# 2_MCU.net
KiCad netlist of a schematic drawn in Altium Designer
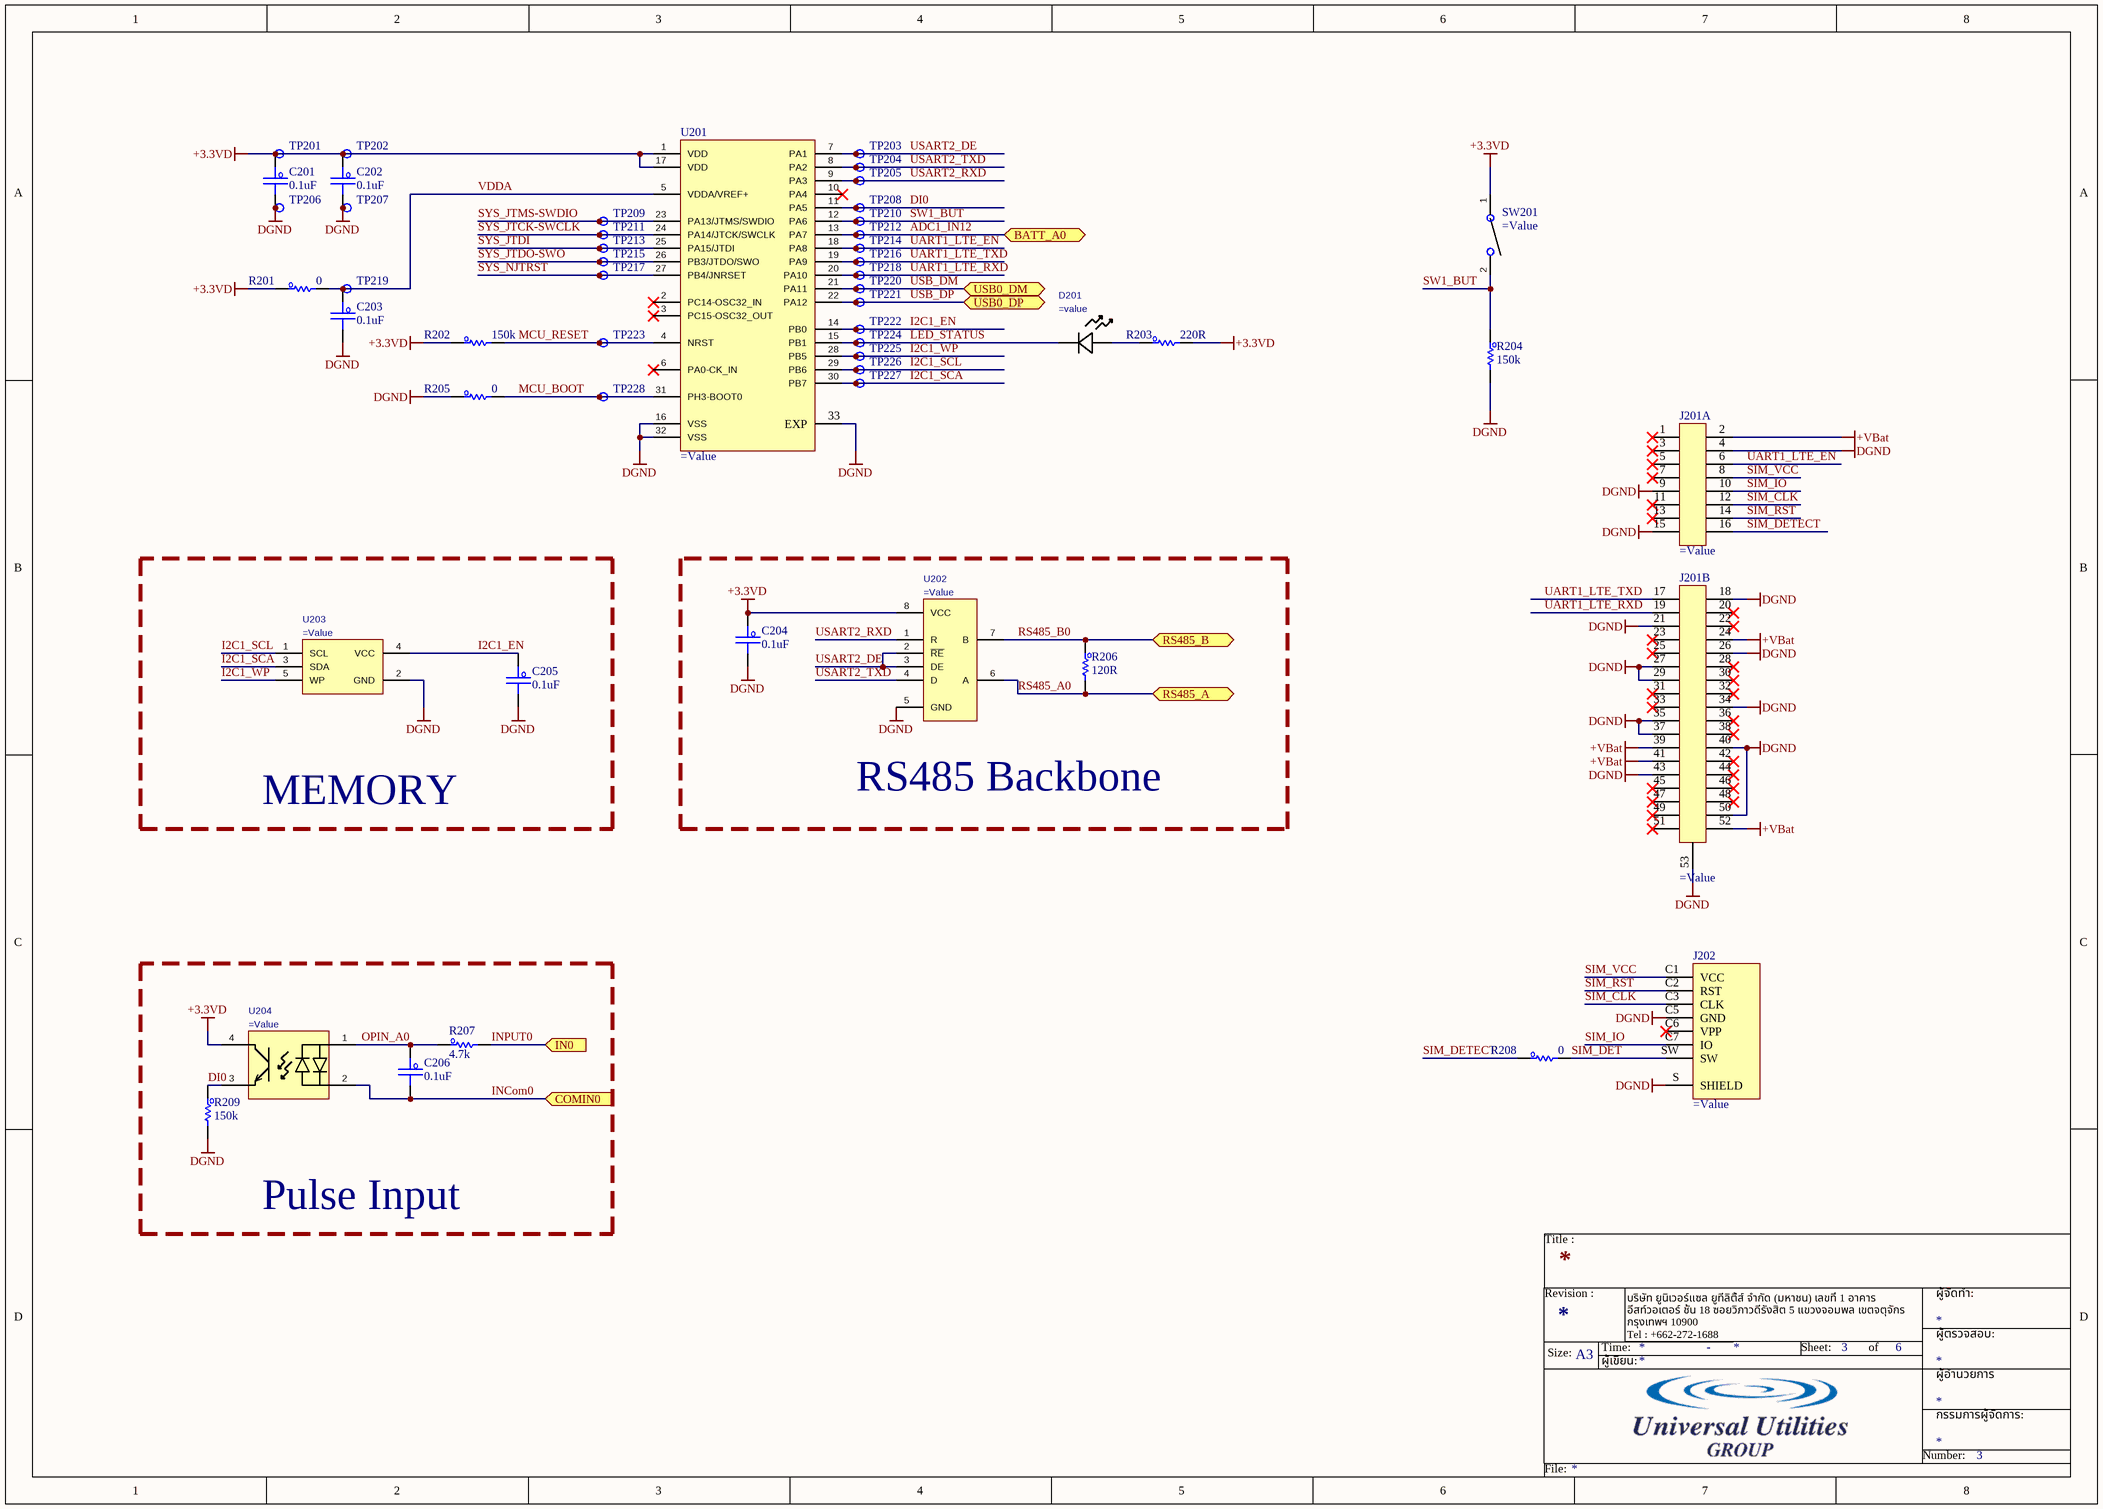
[diagram p0: 2_MCU.SchDoc]

(export (version "E")
  (design (tool "Eeschema 10.0.6"))
  (components
    (comp (ref "C201")
      (value "0.1uF")
      (footprint "C_0603")
      (description "CAP CER 0.1UF 50V X7R 0603")
      (fields (field (name "MANUFACTURER") "KEMET") (field (name "PARTNUMBER") "C0603C104K5RACTU"))
      (libsource (lib "UUSymbol") (part "C_Capacitor"))
    )
    (comp (ref "C202")
      (value "0.1uF")
      (footprint "C_0603")
      (description "CAP CER 0.1UF 50V X7R 0603")
      (fields (field (name "MANUFACTURER") "KEMET") (field (name "PARTNUMBER") "C0603C104K5RACTU"))
      (libsource (lib "UUSymbol") (part "C_Capacitor"))
    )
    (comp (ref "C203")
      (value "0.1uF")
      (footprint "C_0603")
      (description "CAP CER 0.1UF 50V X7R 0603")
      (fields (field (name "MANUFACTURER") "KEMET") (field (name "PARTNUMBER") "C0603C104K5RACTU"))
      (libsource (lib "UUSymbol") (part "C_Capacitor"))
    )
    (comp (ref "C204")
      (value "0.1uF")
      (footprint "C_0603")
      (description "CAP CER 0.1UF 50V X7R 0603")
      (fields (field (name "MANUFACTURER") "KEMET") (field (name "PARTNUMBER") "C0603C104K5RACTU"))
      (libsource (lib "UUSymbol") (part "C_Capacitor"))
    )
    (comp (ref "C205")
      (value "0.1uF")
      (footprint "C_0603")
      (description "CAP CER 0.1UF 50V X7R 0603")
      (fields (field (name "MANUFACTURER") "KEMET") (field (name "PARTNUMBER") "C0603C104K5RACTU"))
      (libsource (lib "UUSymbol") (part "C_Capacitor"))
    )
    (comp (ref "C206")
      (value "0.1uF")
      (footprint "C_0603")
      (description "CAP CER 0.1UF 50V X7R 0603")
      (fields (field (name "MANUFACTURER") "KEMET") (field (name "PARTNUMBER") "C0603C104K5RACTU"))
      (libsource (lib "UUSymbol") (part "C_Capacitor"))
    )
    (comp (ref "D201")
      (value "~")
      (footprint "LED_0VS75000_WRE")
      (description "LED BLUE CLEAR 0603 SMD")
      (fields (field (name "MANUFACTURER") "Wurth Electronics") (field (name "PARTNUMBER") "150060VS75000"))
      (libsource (lib "UUSymbol") (part "D_LED_150060BS75000"))
    )
    (comp (ref "J201")
      (value "~")
      (footprint "TE_2041119-1")
      (description "CONN PCI EXP MINI FEMALE 52POS")
      (fields
        (field (name "PARTNUMBER") "2041119-1")
        (field (name "MANUFACTURER") "TE Connectivity AMP Connectors")
      )
      (libsource (lib "UUSymbol") (part "CON_PCI-E-52P"))
    )
    (comp (ref "J202")
      (value "~")
      (footprint "SIM8060-6-1-14-00-A_REVA")
      (description "CONN SIM NANO HINGED 6P W/SWITCH")
      (fields (field (name "PARTNUMBER") "SIM8060-6-1-14-00-A") (field (name "MANUFACTURER") "GCT"))
      (libsource (lib "UUSymbol") (part "CON_SIM_Nano_Top"))
    )
    (comp (ref "R201")
      (value "0")
      (footprint "R_0603")
      (description "RES SMD 0 OHM JUMP 1/10W 0603")
      (fields (field (name "MANUFACTURER") "Vishay Dale") (field (name "PARTNUMBER") "CRCW06030000Z0EBC"))
      (libsource (lib "UUSymbol") (part "R_Resister"))
    )
    (comp (ref "R202")
      (value "150k")
      (footprint "R_0603")
      (description "RES SMD 150K OHM 1% 1/10W 0603")
      (fields (field (name "MANUFACTURER") "Vishay Dale") (field (name "PARTNUMBER") "CRCW0603150KFKEAC"))
      (libsource (lib "UUSymbol") (part "R_Resister"))
    )
    (comp (ref "R203")
      (value "220R")
      (footprint "R_0603")
      (description "RES SMD 220 OHM 1% 1/10W 0603")
      (fields (field (name "MANUFACTURER") "Vishay Dale") (field (name "PARTNUMBER") "CRCW0603220RFKEAC"))
      (libsource (lib "UUSymbol") (part "R_Resister"))
    )
    (comp (ref "R204")
      (value "150k")
      (footprint "R_0603")
      (description "RES SMD 150K OHM 1% 1/10W 0603")
      (fields (field (name "MANUFACTURER") "Vishay Dale") (field (name "PARTNUMBER") "CRCW0603150KFKEAC"))
      (libsource (lib "UUSymbol") (part "R_Resister"))
    )
    (comp (ref "R205")
      (value "0")
      (footprint "R_0603")
      (description "RES SMD 0 OHM JUMP 1/10W 0603")
      (fields (field (name "MANUFACTURER") "Vishay Dale") (field (name "PARTNUMBER") "CRCW06030000Z0EBC"))
      (libsource (lib "UUSymbol") (part "R_Resister"))
    )
    (comp (ref "R206")
      (value "120R")
      (footprint "R_0603")
      (description "RES SMD 120 OHM 1% 1/3W 0603")
      (fields (field (name "MANUFACTURER") "Vishay Dale") (field (name "PARTNUMBER") "CRCW0603120RFKEAHP"))
      (libsource (lib "UUSymbol") (part "R_Resister"))
    )
    (comp (ref "R207")
      (value "4.7k")
      (footprint "R_0603")
      (description "RES 4.7K OHM 5% 1/10W 0603")
      (fields (field (name "MANUFACTURER") "Vishay Dale") (field (name "PARTNUMBER") "CRCW06034K70JNEBC"))
      (libsource (lib "UUSymbol") (part "R_Resister"))
    )
    (comp (ref "R208")
      (value "0")
      (footprint "R_0603")
      (description "RES SMD 0 OHM JUMP 1/10W 0603")
      (fields (field (name "MANUFACTURER") "Vishay Dale") (field (name "PARTNUMBER") "CRCW06030000Z0EBC"))
      (libsource (lib "UUSymbol") (part "R_Resister"))
    )
    (comp (ref "R209")
      (value "150k")
      (footprint "R_0603")
      (description "RES SMD 150K OHM 1% 1/10W 0603")
      (fields (field (name "MANUFACTURER") "Vishay Dale") (field (name "PARTNUMBER") "CRCW0603150KFKEAC"))
      (libsource (lib "UUSymbol") (part "R_Resister"))
    )
    (comp (ref "SW201")
      (value "~")
      (footprint "SW_KSS241GLFS_CN")
      (description "SWITCH TACTILE SPST-NO 0.05A 50V")
      (fields (field (name "PARTNUMBER") "KSS241GLFS") (field (name "MANUFACTURER") "C&K"))
      (libsource (lib "UUSymbol") (part "SW_TAC"))
    )
    (comp (ref "TP201")
      (value "~")
      (footprint "TP_Testpoint")
      (description "TestPoint")
      (libsource (lib "UUSymbol") (part "TP_TestPoint"))
    )
    (comp (ref "TP202")
      (value "~")
      (footprint "TP_Testpoint")
      (description "TestPoint")
      (libsource (lib "UUSymbol") (part "TP_TestPoint"))
    )
    (comp (ref "TP203")
      (value "~")
      (footprint "TP_Testpoint")
      (description "TestPoint")
      (libsource (lib "UUSymbol") (part "TP_TestPoint"))
    )
    (comp (ref "TP204")
      (value "~")
      (footprint "TP_Testpoint")
      (description "TestPoint")
      (libsource (lib "UUSymbol") (part "TP_TestPoint"))
    )
    (comp (ref "TP205")
      (value "~")
      (footprint "TP_Testpoint")
      (description "TestPoint")
      (libsource (lib "UUSymbol") (part "TP_TestPoint"))
    )
    (comp (ref "TP206")
      (value "~")
      (footprint "TP_Testpoint")
      (description "TestPoint")
      (libsource (lib "UUSymbol") (part "TP_TestPoint"))
    )
    (comp (ref "TP207")
      (value "~")
      (footprint "TP_Testpoint")
      (description "TestPoint")
      (libsource (lib "UUSymbol") (part "TP_TestPoint"))
    )
    (comp (ref "TP208")
      (value "~")
      (footprint "TP_Testpoint")
      (description "TestPoint")
      (libsource (lib "UUSymbol") (part "TP_TestPoint"))
    )
    (comp (ref "TP209")
      (value "~")
      (footprint "TP_Testpoint")
      (description "TestPoint")
      (libsource (lib "UUSymbol") (part "TP_TestPoint"))
    )
    (comp (ref "TP210")
      (value "~")
      (footprint "TP_Testpoint")
      (description "TestPoint")
      (libsource (lib "UUSymbol") (part "TP_TestPoint"))
    )
    (comp (ref "TP211")
      (value "~")
      (footprint "TP_Testpoint")
      (description "TestPoint")
      (libsource (lib "UUSymbol") (part "TP_TestPoint"))
    )
    (comp (ref "TP212")
      (value "~")
      (footprint "TP_Testpoint")
      (description "TestPoint")
      (libsource (lib "UUSymbol") (part "TP_TestPoint"))
    )
    (comp (ref "TP213")
      (value "~")
      (footprint "TP_Testpoint")
      (description "TestPoint")
      (libsource (lib "UUSymbol") (part "TP_TestPoint"))
    )
    (comp (ref "TP214")
      (value "~")
      (footprint "TP_Testpoint")
      (description "TestPoint")
      (libsource (lib "UUSymbol") (part "TP_TestPoint"))
    )
    (comp (ref "TP215")
      (value "~")
      (footprint "TP_Testpoint")
      (description "TestPoint")
      (libsource (lib "UUSymbol") (part "TP_TestPoint"))
    )
    (comp (ref "TP216")
      (value "~")
      (footprint "TP_Testpoint")
      (description "TestPoint")
      (libsource (lib "UUSymbol") (part "TP_TestPoint"))
    )
    (comp (ref "TP217")
      (value "~")
      (footprint "TP_Testpoint")
      (description "TestPoint")
      (libsource (lib "UUSymbol") (part "TP_TestPoint"))
    )
    (comp (ref "TP218")
      (value "~")
      (footprint "TP_Testpoint")
      (description "TestPoint")
      (libsource (lib "UUSymbol") (part "TP_TestPoint"))
    )
    (comp (ref "TP219")
      (value "~")
      (footprint "TP_Testpoint")
      (description "TestPoint")
      (libsource (lib "UUSymbol") (part "TP_TestPoint"))
    )
    (comp (ref "TP220")
      (value "~")
      (footprint "TP_Testpoint")
      (description "TestPoint")
      (libsource (lib "UUSymbol") (part "TP_TestPoint"))
    )
    (comp (ref "TP221")
      (value "~")
      (footprint "TP_Testpoint")
      (description "TestPoint")
      (libsource (lib "UUSymbol") (part "TP_TestPoint"))
    )
    (comp (ref "TP222")
      (value "~")
      (footprint "TP_Testpoint")
      (description "TestPoint")
      (libsource (lib "UUSymbol") (part "TP_TestPoint"))
    )
    (comp (ref "TP223")
      (value "~")
      (footprint "TP_Testpoint")
      (description "TestPoint")
      (libsource (lib "UUSymbol") (part "TP_TestPoint"))
    )
    (comp (ref "TP224")
      (value "~")
      (footprint "TP_Testpoint")
      (description "TestPoint")
      (libsource (lib "UUSymbol") (part "TP_TestPoint"))
    )
    (comp (ref "TP225")
      (value "~")
      (footprint "TP_Testpoint")
      (description "TestPoint")
      (libsource (lib "UUSymbol") (part "TP_TestPoint"))
    )
    (comp (ref "TP226")
      (value "~")
      (footprint "TP_Testpoint")
      (description "TestPoint")
      (libsource (lib "UUSymbol") (part "TP_TestPoint"))
    )
    (comp (ref "TP227")
      (value "~")
      (footprint "TP_Testpoint")
      (description "TestPoint")
      (libsource (lib "UUSymbol") (part "TP_TestPoint"))
    )
    (comp (ref "TP228")
      (value "~")
      (footprint "TP_Testpoint")
      (description "TestPoint")
      (libsource (lib "UUSymbol") (part "TP_TestPoint"))
    )
    (comp (ref "U201")
      (value "~")
      (footprint "QFN50P500X500X60-33N")
      (description "IC MCU 32BIT 256KB FLSH 32UFQFPN")
      (fields (field (name "PARTNUMBER") "STM32L432KCU6") (field (name "MANUFACTURER") "STMicroelectronics"))
      (libsource (lib "UUSymbol") (part "IC_MCU_STM32L432"))
    )
    (comp (ref "U202")
      (value "~")
      (footprint "D0008A_L")
      (description "IC TRANSCEIVER HALF 1/1 8SOIC")
      (fields (field (name "MANUFACTURER") "Texas Instruments") (field (name "PARTNUMBER") "SN65HVD11DR"))
      (libsource (lib "UUSymbol") (part "IC_TRAN_THVD1505DR"))
    )
    (comp (ref "U203")
      (value "~")
      (footprint "SOT65P210X110-5N")
      (description "IC EEPROM 2KBIT I2C SC70-5")
      (fields
        (field (name "MANUFACTURER") "Microchip Technology")
        (field (name "PARTNUMBER") "24AA02HT-I/LT")
      )
      (libsource (lib "UUSymbol") (part "IC_MEM_24AA02HT"))
    )
    (comp (ref "U204")
      (value "~")
      (footprint "SOIC_M618A-3T_VI")
      (description "OPTOISOLATR 5KV TRANSISTOR 4-SMD")
      (fields (field (name "MANUFACTURER") "Lite-On Inc.") (field (name "PARTNUMBER") "LTV-814S-TA1"))
      (libsource (lib "UUSymbol") (part "IC_OPTO_LTV-814S-TA1"))
    )
  )
  (nets
    (net (code "1") (name "+3.3VD") (class "Default")
      (node (ref "C201") (pin "1") (pinfunction "1_1") (pintype "passive"))
      (node (ref "C202") (pin "1") (pinfunction "1_1") (pintype "passive"))
      (node (ref "C204") (pin "1") (pinfunction "1_1") (pintype "passive"))
      (node (ref "R201") (pin "1") (pinfunction "1_1") (pintype "passive"))
      (node (ref "R202") (pin "1") (pinfunction "1_1") (pintype "passive"))
      (node (ref "R203") (pin "2") (pinfunction "2_2") (pintype "passive"))
      (node (ref "SW201") (pin "1") (pinfunction "1_1") (pintype "passive"))
      (node (ref "TP201") (pin "1") (pinfunction "1_1") (pintype "passive"))
      (node (ref "TP202") (pin "1") (pinfunction "1_1") (pintype "passive"))
      (node (ref "U201") (pin "1") (pinfunction "VDD_1") (pintype "passive"))
      (node (ref "U201") (pin "17") (pinfunction "VDD_17") (pintype "passive"))
      (node (ref "U202") (pin "8") (pinfunction "VCC_8") (pintype "passive"))
      (node (ref "U204") (pin "4") (pinfunction "C_4") (pintype "passive"))
    )
    (net (code "2") (name "+VBat") (class "Default")
      (node (ref "J201") (pin "2") (pinfunction "2_2") (pintype "passive"))
      (node (ref "J201") (pin "24") (pinfunction "24_24") (pintype "passive"))
      (node (ref "J201") (pin "39") (pinfunction "39_39") (pintype "passive"))
      (node (ref "J201") (pin "41") (pinfunction "41_41") (pintype "passive"))
      (node (ref "J201") (pin "52") (pinfunction "52_52") (pintype "passive"))
    )
    (net (code "3") (name "/ADC1_IN12") (class "Default")
      (node (ref "TP212") (pin "1") (pinfunction "1_1") (pintype "passive"))
      (node (ref "U201") (pin "13") (pinfunction "PA7_13") (pintype "passive"))
    )
    (net (code "4") (name "/DI0") (class "Default")
      (node (ref "R209") (pin "1") (pinfunction "1_1") (pintype "passive"))
      (node (ref "TP208") (pin "1") (pinfunction "1_1") (pintype "passive"))
      (node (ref "U201") (pin "11") (pinfunction "PA5_11") (pintype "passive"))
      (node (ref "U204") (pin "3") (pinfunction "E_3") (pintype "passive"))
    )
    (net (code "5") (name "/I2C1_EN") (class "Default")
      (node (ref "C205") (pin "1") (pinfunction "1_1") (pintype "passive"))
      (node (ref "TP222") (pin "1") (pinfunction "1_1") (pintype "passive"))
      (node (ref "U201") (pin "14") (pinfunction "PB0_14") (pintype "passive"))
      (node (ref "U203") (pin "4") (pinfunction "VCC_4") (pintype "passive"))
    )
    (net (code "6") (name "/I2C1_SCA") (class "Default")
      (node (ref "TP227") (pin "1") (pinfunction "1_1") (pintype "passive"))
      (node (ref "U201") (pin "30") (pinfunction "PB7_30") (pintype "passive"))
      (node (ref "U203") (pin "3") (pinfunction "SDA_3") (pintype "passive"))
    )
    (net (code "7") (name "/I2C1_SCL") (class "Default")
      (node (ref "TP226") (pin "1") (pinfunction "1_1") (pintype "passive"))
      (node (ref "U201") (pin "29") (pinfunction "PB6_29") (pintype "passive"))
      (node (ref "U203") (pin "1") (pinfunction "SCL_1") (pintype "passive"))
    )
    (net (code "8") (name "/I2C1_WP") (class "Default")
      (node (ref "TP225") (pin "1") (pinfunction "1_1") (pintype "passive"))
      (node (ref "U201") (pin "28") (pinfunction "PB5_28") (pintype "passive"))
      (node (ref "U203") (pin "5") (pinfunction "WP_5") (pintype "passive"))
    )
    (net (code "9") (name "/INCom0") (class "Default")
      (node (ref "C206") (pin "2") (pinfunction "2_2") (pintype "passive"))
      (node (ref "U204") (pin "2") (pinfunction "C_2_2") (pintype "passive"))
    )
    (net (code "10") (name "/INPUT0") (class "Default")
      (node (ref "R207") (pin "2") (pinfunction "2_2") (pintype "passive"))
    )
    (net (code "11") (name "/LED_STATUS") (class "Default")
      (node (ref "D201") (pin "2") (pinfunction "2_2") (pintype "passive"))
      (node (ref "TP224") (pin "1") (pinfunction "1_1") (pintype "passive"))
      (node (ref "U201") (pin "15") (pinfunction "PB1_15") (pintype "passive"))
    )
    (net (code "12") (name "/MCU_BOOT") (class "Default")
      (node (ref "R205") (pin "2") (pinfunction "2_2") (pintype "passive"))
      (node (ref "TP228") (pin "1") (pinfunction "1_1") (pintype "passive"))
      (node (ref "U201") (pin "31") (pinfunction "PH3-BOOT0_31") (pintype "passive"))
    )
    (net (code "13") (name "/MCU_RESET") (class "Default")
      (node (ref "R202") (pin "2") (pinfunction "2_2") (pintype "passive"))
      (node (ref "TP223") (pin "1") (pinfunction "1_1") (pintype "passive"))
      (node (ref "U201") (pin "4") (pinfunction "NRST_4") (pintype "passive"))
    )
    (net (code "14") (name "/OPIN_A0") (class "Default")
      (node (ref "C206") (pin "1") (pinfunction "1_1") (pintype "passive"))
      (node (ref "R207") (pin "1") (pinfunction "1_1") (pintype "passive"))
      (node (ref "U204") (pin "1") (pinfunction "A_1") (pintype "passive"))
    )
    (net (code "15") (name "/RS485_A0") (class "Default")
      (node (ref "R206") (pin "2") (pinfunction "2_2") (pintype "passive"))
      (node (ref "U202") (pin "6") (pinfunction "A_6") (pintype "passive"))
    )
    (net (code "16") (name "/RS485_B0") (class "Default")
      (node (ref "R206") (pin "1") (pinfunction "1_1") (pintype "passive"))
      (node (ref "U202") (pin "7") (pinfunction "B_7") (pintype "passive"))
    )
    (net (code "17") (name "/SIM_CLK") (class "Default")
      (node (ref "J201") (pin "12") (pinfunction "12_12") (pintype "passive"))
      (node (ref "J202") (pin "C3") (pinfunction "CLK_C3") (pintype "passive"))
    )
    (net (code "18") (name "/SIM_DET") (class "Default")
      (node (ref "J202") (pin "SW") (pinfunction "SW_SW") (pintype "passive"))
      (node (ref "R208") (pin "2") (pinfunction "2_2") (pintype "passive"))
    )
    (net (code "19") (name "/SIM_DETECT") (class "Default")
      (node (ref "J201") (pin "16") (pinfunction "16_16") (pintype "passive"))
      (node (ref "R208") (pin "1") (pinfunction "1_1") (pintype "passive"))
    )
    (net (code "20") (name "/SIM_IO") (class "Default")
      (node (ref "J201") (pin "10") (pinfunction "10_10") (pintype "passive"))
      (node (ref "J202") (pin "C7") (pinfunction "IO_C7") (pintype "passive"))
    )
    (net (code "21") (name "/SIM_RST") (class "Default")
      (node (ref "J201") (pin "14") (pinfunction "14_14") (pintype "passive"))
      (node (ref "J202") (pin "C2") (pinfunction "RST_C2") (pintype "passive"))
    )
    (net (code "22") (name "/SIM_VCC") (class "Default")
      (node (ref "J201") (pin "8") (pinfunction "8_8") (pintype "passive"))
      (node (ref "J202") (pin "C1") (pinfunction "VCC_C1") (pintype "passive"))
    )
    (net (code "23") (name "/SW1_BUT") (class "Default")
      (node (ref "R204") (pin "1") (pinfunction "1_1") (pintype "passive"))
      (node (ref "SW201") (pin "2") (pinfunction "2_2") (pintype "passive"))
      (node (ref "TP210") (pin "1") (pinfunction "1_1") (pintype "passive"))
      (node (ref "U201") (pin "12") (pinfunction "PA6_12") (pintype "passive"))
    )
    (net (code "24") (name "/SYS_JTCK-SWCLK") (class "Default")
      (node (ref "TP211") (pin "1") (pinfunction "1_1") (pintype "passive"))
      (node (ref "U201") (pin "24") (pinfunction "PA14/JTCK/SWCLK_24") (pintype "passive"))
    )
    (net (code "25") (name "/SYS_JTDI") (class "Default")
      (node (ref "TP213") (pin "1") (pinfunction "1_1") (pintype "passive"))
      (node (ref "U201") (pin "25") (pinfunction "PA15/JTDI_25") (pintype "passive"))
    )
    (net (code "26") (name "/SYS_JTDO-SWO") (class "Default")
      (node (ref "TP215") (pin "1") (pinfunction "1_1") (pintype "passive"))
      (node (ref "U201") (pin "26") (pinfunction "PB3/JTDO/SWO_26") (pintype "passive"))
    )
    (net (code "27") (name "/SYS_JTMS-SWDIO") (class "Default")
      (node (ref "TP209") (pin "1") (pinfunction "1_1") (pintype "passive"))
      (node (ref "U201") (pin "23") (pinfunction "PA13/JTMS/SWDIO_23") (pintype "passive"))
    )
    (net (code "28") (name "/SYS_NJTRST") (class "Default")
      (node (ref "TP217") (pin "1") (pinfunction "1_1") (pintype "passive"))
      (node (ref "U201") (pin "27") (pinfunction "PB4/JNRSET_27") (pintype "passive"))
    )
    (net (code "29") (name "/UART1_LTE_EN") (class "Default")
      (node (ref "J201") (pin "6") (pinfunction "6_6") (pintype "passive"))
      (node (ref "TP214") (pin "1") (pinfunction "1_1") (pintype "passive"))
      (node (ref "U201") (pin "18") (pinfunction "PA8_18") (pintype "passive"))
    )
    (net (code "30") (name "/UART1_LTE_RXD") (class "Default")
      (node (ref "J201") (pin "19") (pinfunction "19_19") (pintype "passive"))
      (node (ref "TP218") (pin "1") (pinfunction "1_1") (pintype "passive"))
      (node (ref "U201") (pin "20") (pinfunction "PA10_20") (pintype "passive"))
    )
    (net (code "31") (name "/UART1_LTE_TXD") (class "Default")
      (node (ref "J201") (pin "17") (pinfunction "17_17") (pintype "passive"))
      (node (ref "TP216") (pin "1") (pinfunction "1_1") (pintype "passive"))
      (node (ref "U201") (pin "19") (pinfunction "PA9_19") (pintype "passive"))
    )
    (net (code "32") (name "/USART2_DE") (class "Default")
      (node (ref "TP203") (pin "1") (pinfunction "1_1") (pintype "passive"))
      (node (ref "U201") (pin "7") (pinfunction "PA1_7") (pintype "passive"))
      (node (ref "U202") (pin "2") (pinfunction "~{RE}_2") (pintype "passive"))
      (node (ref "U202") (pin "3") (pinfunction "DE_3") (pintype "passive"))
    )
    (net (code "33") (name "/USART2_RXD") (class "Default")
      (node (ref "TP205") (pin "1") (pinfunction "1_1") (pintype "passive"))
      (node (ref "U201") (pin "9") (pinfunction "PA3_9") (pintype "passive"))
      (node (ref "U202") (pin "1") (pinfunction "R_1") (pintype "passive"))
    )
    (net (code "34") (name "/USART2_TXD") (class "Default")
      (node (ref "TP204") (pin "1") (pinfunction "1_1") (pintype "passive"))
      (node (ref "U201") (pin "8") (pinfunction "PA2_8") (pintype "passive"))
      (node (ref "U202") (pin "4") (pinfunction "D_4") (pintype "passive"))
    )
    (net (code "35") (name "/USB_DM") (class "Default")
      (node (ref "TP220") (pin "1") (pinfunction "1_1") (pintype "passive"))
      (node (ref "U201") (pin "21") (pinfunction "PA11_21") (pintype "passive"))
    )
    (net (code "36") (name "/USB_DP") (class "Default")
      (node (ref "TP221") (pin "1") (pinfunction "1_1") (pintype "passive"))
      (node (ref "U201") (pin "22") (pinfunction "PA12_22") (pintype "passive"))
    )
    (net (code "37") (name "/VDDA") (class "Default")
      (node (ref "C203") (pin "1") (pinfunction "1_1") (pintype "passive"))
      (node (ref "R201") (pin "2") (pinfunction "2_2") (pintype "passive"))
      (node (ref "TP219") (pin "1") (pinfunction "1_1") (pintype "passive"))
      (node (ref "U201") (pin "5") (pinfunction "VDDA/VREF+_5") (pintype "passive"))
    )
    (net (code "38") (name "DGND") (class "Default")
      (node (ref "C201") (pin "2") (pinfunction "2_2") (pintype "passive"))
      (node (ref "C202") (pin "2") (pinfunction "2_2") (pintype "passive"))
      (node (ref "C203") (pin "2") (pinfunction "2_2") (pintype "passive"))
      (node (ref "C204") (pin "2") (pinfunction "2_2") (pintype "passive"))
      (node (ref "C205") (pin "2") (pinfunction "2_2") (pintype "passive"))
      (node (ref "J201") (pin "15") (pinfunction "15_15") (pintype "passive"))
      (node (ref "J201") (pin "18") (pinfunction "18_18") (pintype "passive"))
      (node (ref "J201") (pin "21") (pinfunction "21_21") (pintype "passive"))
      (node (ref "J201") (pin "26") (pinfunction "26_26") (pintype "passive"))
      (node (ref "J201") (pin "27") (pinfunction "27_27") (pintype "passive"))
      (node (ref "J201") (pin "29") (pinfunction "29_29") (pintype "passive"))
      (node (ref "J201") (pin "34") (pinfunction "34_34") (pintype "passive"))
      (node (ref "J201") (pin "35") (pinfunction "35_35") (pintype "passive"))
      (node (ref "J201") (pin "37") (pinfunction "37_37") (pintype "passive"))
      (node (ref "J201") (pin "4") (pinfunction "4_4") (pintype "passive"))
      (node (ref "J201") (pin "40") (pinfunction "40_40") (pintype "passive"))
      (node (ref "J201") (pin "43") (pinfunction "43_43") (pintype "passive"))
      (node (ref "J201") (pin "50") (pinfunction "50_50") (pintype "passive"))
      (node (ref "J201") (pin "53") (pinfunction "53_53") (pintype "passive"))
      (node (ref "J201") (pin "9") (pinfunction "9_9") (pintype "passive"))
      (node (ref "J202") (pin "C5") (pinfunction "GND_C5") (pintype "passive"))
      (node (ref "J202") (pin "S") (pinfunction "SHIELD_S") (pintype "passive"))
      (node (ref "R204") (pin "2") (pinfunction "2_2") (pintype "passive"))
      (node (ref "R205") (pin "1") (pinfunction "1_1") (pintype "passive"))
      (node (ref "R209") (pin "2") (pinfunction "2_2") (pintype "passive"))
      (node (ref "TP206") (pin "1") (pinfunction "1_1") (pintype "passive"))
      (node (ref "TP207") (pin "1") (pinfunction "1_1") (pintype "passive"))
      (node (ref "U201") (pin "16") (pinfunction "VSS_16") (pintype "passive"))
      (node (ref "U201") (pin "32") (pinfunction "VSS_32") (pintype "passive"))
      (node (ref "U201") (pin "33") (pinfunction "EXP_33") (pintype "passive"))
      (node (ref "U202") (pin "5") (pinfunction "GND_5") (pintype "passive"))
      (node (ref "U203") (pin "2") (pinfunction "GND_2") (pintype "passive"))
    )
    (net (code "39") (name "Net-(D201-Pad1)") (class "Default")
      (node (ref "D201") (pin "1") (pinfunction "1_1") (pintype "passive"))
      (node (ref "R203") (pin "1") (pinfunction "1_1") (pintype "passive"))
    )
    (net (code "40") (name "unconnected-(J201-Pad1)") (class "Default")
      (node (ref "J201") (pin "1") (pinfunction "1_1") (pintype "passive+no_connect"))
    )
    (net (code "41") (name "unconnected-(J201-Pad3)") (class "Default")
      (node (ref "J201") (pin "3") (pinfunction "3_3") (pintype "passive+no_connect"))
    )
    (net (code "42") (name "unconnected-(J201-Pad5)") (class "Default")
      (node (ref "J201") (pin "5") (pinfunction "5_5") (pintype "passive+no_connect"))
    )
    (net (code "43") (name "unconnected-(J201-Pad7)") (class "Default")
      (node (ref "J201") (pin "7") (pinfunction "7_7") (pintype "passive+no_connect"))
    )
    (net (code "44") (name "unconnected-(J201-Pad11)") (class "Default")
      (node (ref "J201") (pin "11") (pinfunction "11_11") (pintype "passive+no_connect"))
    )
    (net (code "45") (name "unconnected-(J201-Pad13)") (class "Default")
      (node (ref "J201") (pin "13") (pinfunction "13_13") (pintype "passive+no_connect"))
    )
    (net (code "46") (name "unconnected-(J201-Pad20)") (class "Default")
      (node (ref "J201") (pin "20") (pinfunction "20_20") (pintype "passive+no_connect"))
    )
    (net (code "47") (name "unconnected-(J201-Pad22)") (class "Default")
      (node (ref "J201") (pin "22") (pinfunction "22_22") (pintype "passive+no_connect"))
    )
    (net (code "48") (name "unconnected-(J201-Pad23)") (class "Default")
      (node (ref "J201") (pin "23") (pinfunction "23_23") (pintype "passive+no_connect"))
    )
    (net (code "49") (name "unconnected-(J201-Pad25)") (class "Default")
      (node (ref "J201") (pin "25") (pinfunction "25_25") (pintype "passive+no_connect"))
    )
    (net (code "50") (name "unconnected-(J201-Pad28)") (class "Default")
      (node (ref "J201") (pin "28") (pinfunction "28_28") (pintype "passive+no_connect"))
    )
    (net (code "51") (name "unconnected-(J201-Pad30)") (class "Default")
      (node (ref "J201") (pin "30") (pinfunction "30_30") (pintype "passive+no_connect"))
    )
    (net (code "52") (name "unconnected-(J201-Pad31)") (class "Default")
      (node (ref "J201") (pin "31") (pinfunction "31_31") (pintype "passive+no_connect"))
    )
    (net (code "53") (name "unconnected-(J201-Pad32)") (class "Default")
      (node (ref "J201") (pin "32") (pinfunction "32_32") (pintype "passive+no_connect"))
    )
    (net (code "54") (name "unconnected-(J201-Pad33)") (class "Default")
      (node (ref "J201") (pin "33") (pinfunction "33_33") (pintype "passive+no_connect"))
    )
    (net (code "55") (name "unconnected-(J201-Pad36)") (class "Default")
      (node (ref "J201") (pin "36") (pinfunction "36_36") (pintype "passive+no_connect"))
    )
    (net (code "56") (name "unconnected-(J201-Pad38)") (class "Default")
      (node (ref "J201") (pin "38") (pinfunction "38_38") (pintype "passive+no_connect"))
    )
    (net (code "57") (name "unconnected-(J201-Pad42)") (class "Default")
      (node (ref "J201") (pin "42") (pinfunction "42_42") (pintype "passive+no_connect"))
    )
    (net (code "58") (name "unconnected-(J201-Pad44)") (class "Default")
      (node (ref "J201") (pin "44") (pinfunction "44_44") (pintype "passive+no_connect"))
    )
    (net (code "59") (name "unconnected-(J201-Pad45)") (class "Default")
      (node (ref "J201") (pin "45") (pinfunction "45_45") (pintype "passive+no_connect"))
    )
    (net (code "60") (name "unconnected-(J201-Pad46)") (class "Default")
      (node (ref "J201") (pin "46") (pinfunction "46_46") (pintype "passive+no_connect"))
    )
    (net (code "61") (name "unconnected-(J201-Pad47)") (class "Default")
      (node (ref "J201") (pin "47") (pinfunction "47_47") (pintype "passive+no_connect"))
    )
    (net (code "62") (name "unconnected-(J201-Pad48)") (class "Default")
      (node (ref "J201") (pin "48") (pinfunction "48_48") (pintype "passive+no_connect"))
    )
    (net (code "63") (name "unconnected-(J201-Pad49)") (class "Default")
      (node (ref "J201") (pin "49") (pinfunction "49_49") (pintype "passive+no_connect"))
    )
    (net (code "64") (name "unconnected-(J201-Pad51)") (class "Default")
      (node (ref "J201") (pin "51") (pinfunction "51_51") (pintype "passive+no_connect"))
    )
    (net (code "65") (name "unconnected-(J202-VPP-PadC6)") (class "Default")
      (node (ref "J202") (pin "C6") (pinfunction "VPP_C6") (pintype "passive+no_connect"))
    )
    (net (code "66") (name "unconnected-(U201-PA0-CK_IN-Pad6)") (class "Default")
      (node (ref "U201") (pin "6") (pinfunction "PA0-CK_IN_6") (pintype "passive+no_connect"))
    )
    (net (code "67") (name "unconnected-(U201-PA4-Pad10)") (class "Default")
      (node (ref "U201") (pin "10") (pinfunction "PA4_10") (pintype "passive+no_connect"))
    )
    (net (code "68") (name "unconnected-(U201-PC14-OSC32_IN-Pad2)") (class "Default")
      (node (ref "U201") (pin "2") (pinfunction "PC14-OSC32_IN_2") (pintype "passive+no_connect"))
    )
    (net (code "69") (name "unconnected-(U201-PC15-OSC32_OUT-Pad3)") (class "Default")
      (node (ref "U201") (pin "3") (pinfunction "PC15-OSC32_OUT_3") (pintype "passive+no_connect"))
    )
  )
)
